# FeatherTestPointBreakout.net
KiCad netlist of a schematic drawn in EAGLE
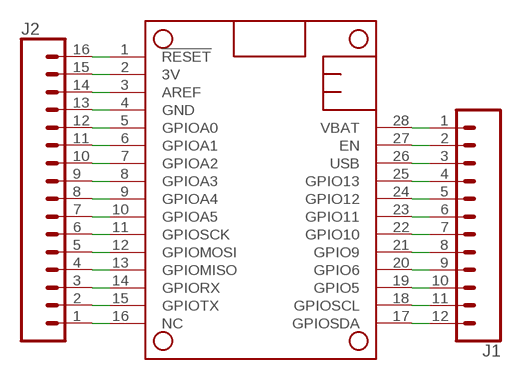
[diagram p0: schematic, sheet 1]

(export (version "E")
  (design (tool "Eeschema 10.0.6"))
  (components
    (comp (ref "J1")
      (value "CONN_12")
      (footprint "eagle-import:1X12")
      (libsource (lib "eagle-import") (part "CONN_12"))
    )
    (comp (ref "J2")
      (value "CONN_16")
      (footprint "eagle-import:1X16")
      (libsource (lib "eagle-import") (part "CONN_16"))
    )
    (comp (ref "MS1")
      (value "FEATHERWINGLAYOUT")
      (footprint "eagle-import:FEATHERWING_MIN")
      (libsource (lib "eagle-import") (part "FEATHERWINGLAYOUT"))
    )
  )
  (nets
    (net (code "1") (name "Net-(MS1-3V)") (class "Default")
      (node (ref "J2") (pin "15") (pinfunction "15_15") (pintype "passive"))
      (node (ref "MS1") (pin "2") (pinfunction "3V_2") (pintype "power_in"))
    )
    (net (code "2") (name "Net-(MS1-AREF)") (class "Default")
      (node (ref "J2") (pin "14") (pinfunction "14_14") (pintype "passive"))
      (node (ref "MS1") (pin "3") (pinfunction "AREF_3") (pintype "passive"))
    )
    (net (code "3") (name "Net-(MS1-EN)") (class "Default")
      (node (ref "J1") (pin "2") (pinfunction "2_2") (pintype "passive"))
      (node (ref "MS1") (pin "27") (pinfunction "EN_27") (pintype "passive"))
    )
    (net (code "4") (name "Net-(MS1-GND)") (class "Default")
      (node (ref "J2") (pin "13") (pinfunction "13_13") (pintype "passive"))
      (node (ref "MS1") (pin "4") (pinfunction "GND_4") (pintype "power_in"))
    )
    (net (code "5") (name "Net-(MS1-GPIO5)") (class "Default")
      (node (ref "J1") (pin "10") (pinfunction "10_10") (pintype "passive"))
      (node (ref "MS1") (pin "19") (pinfunction "GPIO5_19") (pintype "bidirectional"))
    )
    (net (code "6") (name "Net-(MS1-GPIO6)") (class "Default")
      (node (ref "J1") (pin "9") (pinfunction "9_9") (pintype "passive"))
      (node (ref "MS1") (pin "20") (pinfunction "GPIO6_20") (pintype "bidirectional"))
    )
    (net (code "7") (name "Net-(MS1-GPIO9)") (class "Default")
      (node (ref "J1") (pin "8") (pinfunction "8_8") (pintype "passive"))
      (node (ref "MS1") (pin "21") (pinfunction "GPIO9_21") (pintype "bidirectional"))
    )
    (net (code "8") (name "Net-(MS1-GPIO10)") (class "Default")
      (node (ref "J1") (pin "7") (pinfunction "7_7") (pintype "passive"))
      (node (ref "MS1") (pin "22") (pinfunction "GPIO10_22") (pintype "bidirectional"))
    )
    (net (code "9") (name "Net-(MS1-GPIO11)") (class "Default")
      (node (ref "J1") (pin "6") (pinfunction "6_6") (pintype "passive"))
      (node (ref "MS1") (pin "23") (pinfunction "GPIO11_23") (pintype "bidirectional"))
    )
    (net (code "10") (name "Net-(MS1-GPIO12)") (class "Default")
      (node (ref "J1") (pin "5") (pinfunction "5_5") (pintype "passive"))
      (node (ref "MS1") (pin "24") (pinfunction "GPIO12_24") (pintype "bidirectional"))
    )
    (net (code "11") (name "Net-(MS1-GPIO13)") (class "Default")
      (node (ref "J1") (pin "4") (pinfunction "4_4") (pintype "passive"))
      (node (ref "MS1") (pin "25") (pinfunction "GPIO13_25") (pintype "bidirectional"))
    )
    (net (code "12") (name "Net-(MS1-GPIOA0)") (class "Default")
      (node (ref "J2") (pin "12") (pinfunction "12_12") (pintype "passive"))
      (node (ref "MS1") (pin "5") (pinfunction "GPIOA0_5") (pintype "bidirectional"))
    )
    (net (code "13") (name "Net-(MS1-GPIOA1)") (class "Default")
      (node (ref "J2") (pin "11") (pinfunction "11_11") (pintype "passive"))
      (node (ref "MS1") (pin "6") (pinfunction "GPIOA1_6") (pintype "bidirectional"))
    )
    (net (code "14") (name "Net-(MS1-GPIOA2)") (class "Default")
      (node (ref "J2") (pin "10") (pinfunction "10_10") (pintype "passive"))
      (node (ref "MS1") (pin "7") (pinfunction "GPIOA2_7") (pintype "bidirectional"))
    )
    (net (code "15") (name "Net-(MS1-GPIOA3)") (class "Default")
      (node (ref "J2") (pin "9") (pinfunction "9_9") (pintype "passive"))
      (node (ref "MS1") (pin "8") (pinfunction "GPIOA3_8") (pintype "bidirectional"))
    )
    (net (code "16") (name "Net-(MS1-GPIOA4)") (class "Default")
      (node (ref "J2") (pin "8") (pinfunction "8_8") (pintype "passive"))
      (node (ref "MS1") (pin "9") (pinfunction "GPIOA4_9") (pintype "bidirectional"))
    )
    (net (code "17") (name "Net-(MS1-GPIOA5)") (class "Default")
      (node (ref "J2") (pin "7") (pinfunction "7_7") (pintype "passive"))
      (node (ref "MS1") (pin "10") (pinfunction "GPIOA5_10") (pintype "bidirectional"))
    )
    (net (code "18") (name "Net-(MS1-GPIOMISO)") (class "Default")
      (node (ref "J2") (pin "4") (pinfunction "4_4") (pintype "passive"))
      (node (ref "MS1") (pin "13") (pinfunction "GPIOMISO_13") (pintype "bidirectional"))
    )
    (net (code "19") (name "Net-(MS1-GPIOMOSI)") (class "Default")
      (node (ref "J2") (pin "5") (pinfunction "5_5") (pintype "passive"))
      (node (ref "MS1") (pin "12") (pinfunction "GPIOMOSI_12") (pintype "bidirectional"))
    )
    (net (code "20") (name "Net-(MS1-GPIORX)") (class "Default")
      (node (ref "J2") (pin "3") (pinfunction "3_3") (pintype "passive"))
      (node (ref "MS1") (pin "14") (pinfunction "GPIORX_14") (pintype "bidirectional"))
    )
    (net (code "21") (name "Net-(MS1-GPIOSCK)") (class "Default")
      (node (ref "J2") (pin "6") (pinfunction "6_6") (pintype "passive"))
      (node (ref "MS1") (pin "11") (pinfunction "GPIOSCK_11") (pintype "bidirectional"))
    )
    (net (code "22") (name "Net-(MS1-GPIOSCL)") (class "Default")
      (node (ref "J1") (pin "11") (pinfunction "11_11") (pintype "passive"))
      (node (ref "MS1") (pin "18") (pinfunction "GPIOSCL_18") (pintype "bidirectional"))
    )
    (net (code "23") (name "Net-(MS1-GPIOSDA)") (class "Default")
      (node (ref "J1") (pin "12") (pinfunction "12_12") (pintype "passive"))
      (node (ref "MS1") (pin "17") (pinfunction "GPIOSDA_17") (pintype "bidirectional"))
    )
    (net (code "24") (name "Net-(MS1-GPIOTX)") (class "Default")
      (node (ref "J2") (pin "2") (pinfunction "2_2") (pintype "passive"))
      (node (ref "MS1") (pin "15") (pinfunction "GPIOTX_15") (pintype "bidirectional"))
    )
    (net (code "25") (name "Net-(MS1-NC)") (class "Default")
      (node (ref "J2") (pin "1") (pinfunction "1_1") (pintype "passive"))
      (node (ref "MS1") (pin "16") (pinfunction "NC_16") (pintype "passive"))
    )
    (net (code "26") (name "Net-(MS1-USB)") (class "Default")
      (node (ref "J1") (pin "3") (pinfunction "3_3") (pintype "passive"))
      (node (ref "MS1") (pin "26") (pinfunction "USB_26") (pintype "power_in"))
    )
    (net (code "27") (name "Net-(MS1-VBAT)") (class "Default")
      (node (ref "J1") (pin "1") (pinfunction "1_1") (pintype "passive"))
      (node (ref "MS1") (pin "28") (pinfunction "VBAT_28") (pintype "power_in"))
    )
    (net (code "28") (name "Net-(MS1-~{RESET})") (class "Default")
      (node (ref "J2") (pin "16") (pinfunction "16_16") (pintype "passive"))
      (node (ref "MS1") (pin "1") (pinfunction "~{RESET}_1") (pintype "input"))
    )
  )
)
